# Teensy_board.net
KiCad netlist of a schematic drawn in EAGLE
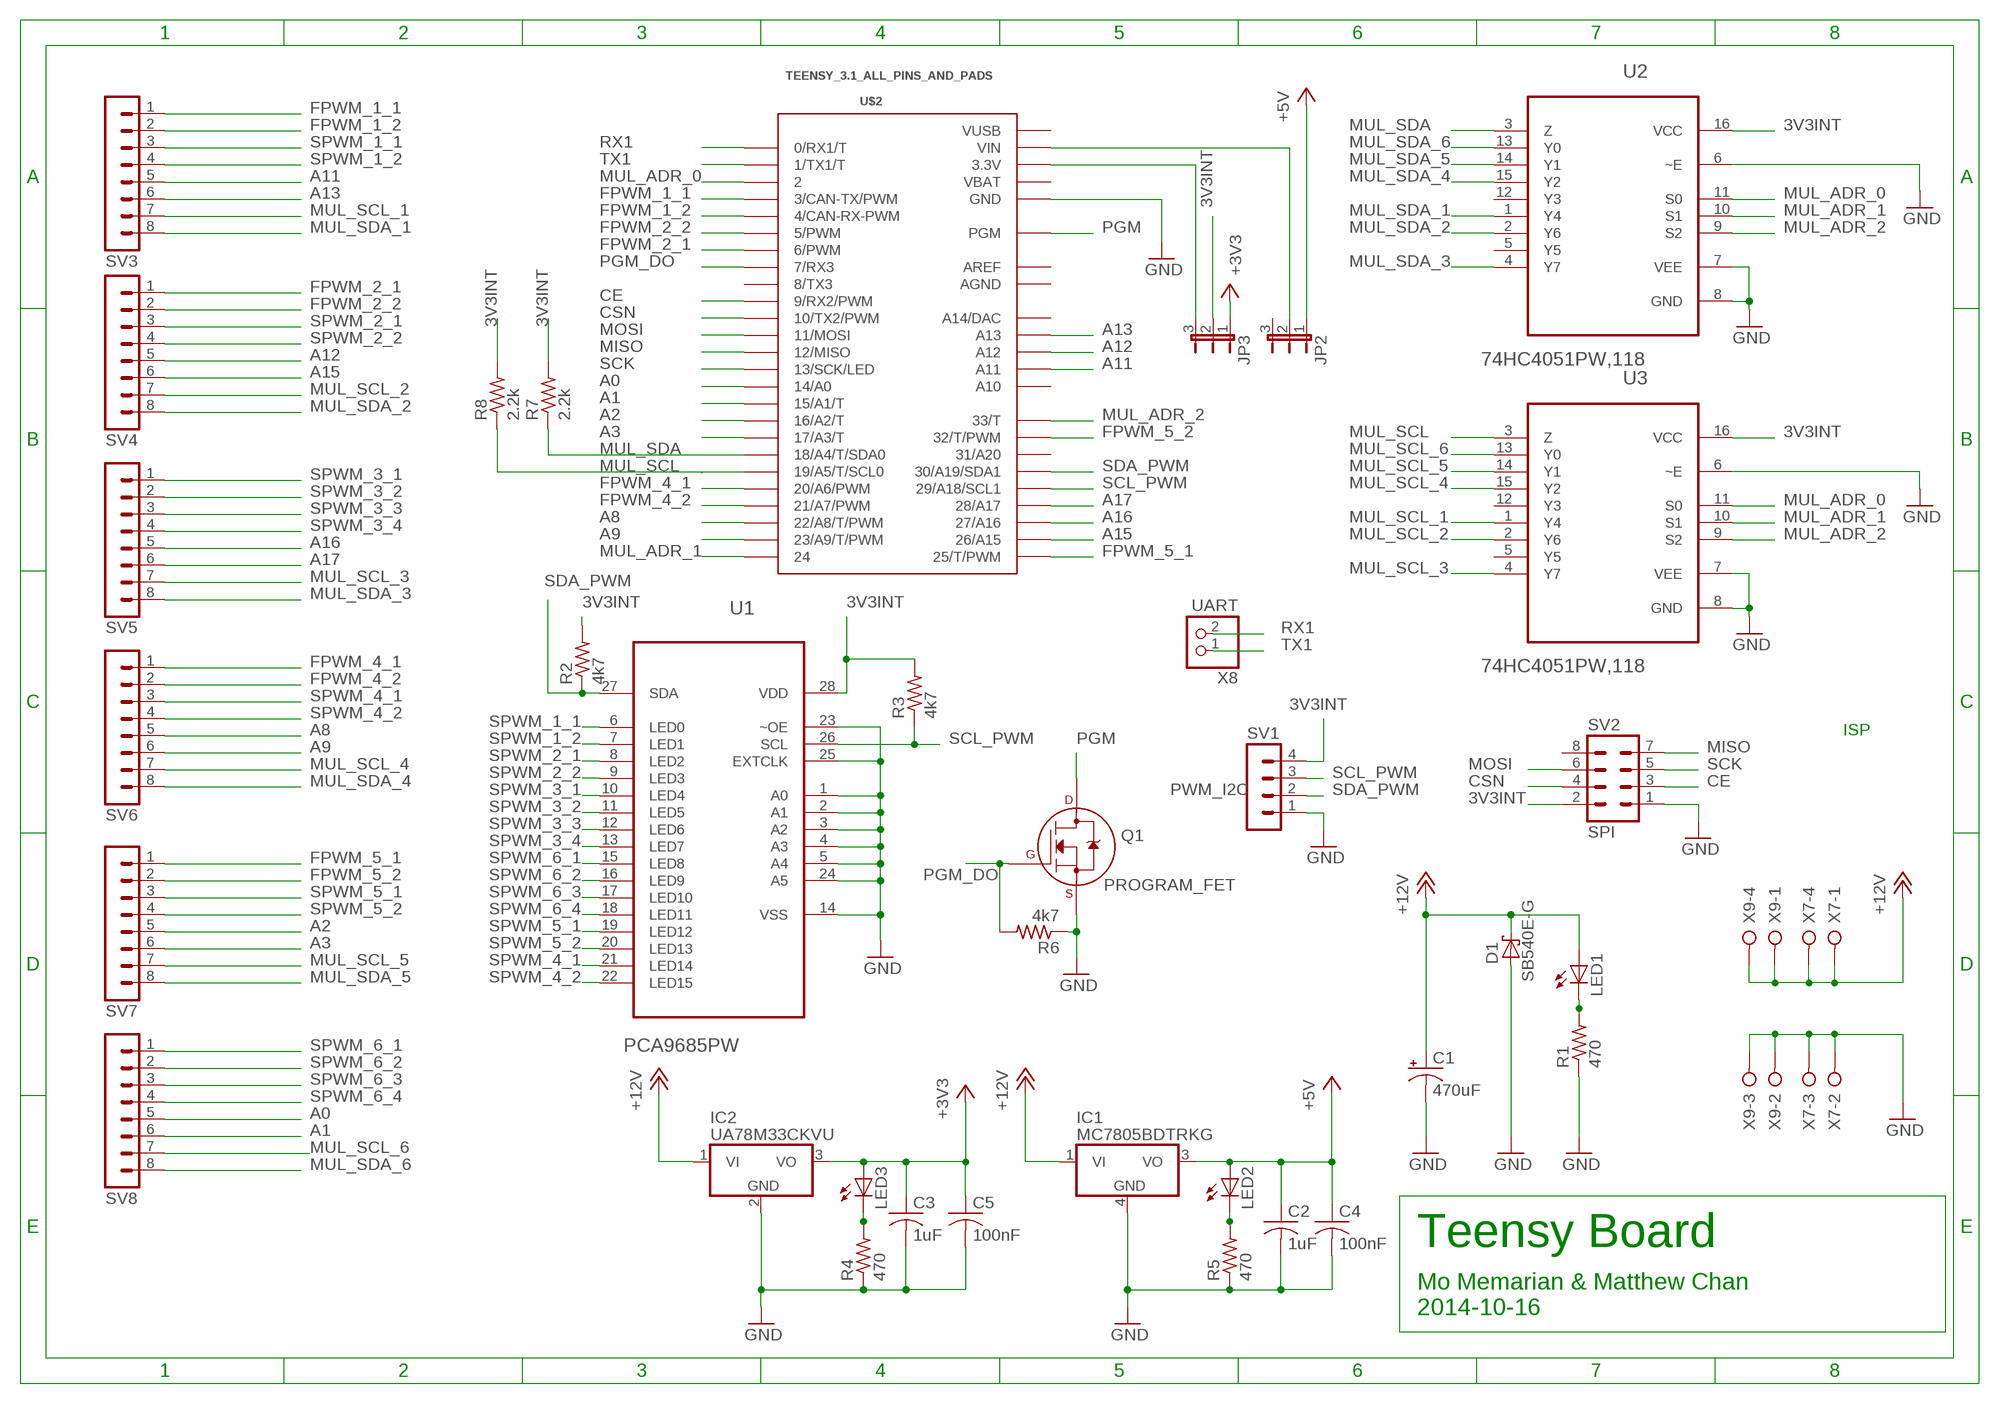
[diagram p0: schematic, sheet 1]

(export (version "E")
  (design (tool "Eeschema 10.0.6"))
  (components
    (comp (ref "C1")
      (value "470uF")
      (footprint "eagle-import:E5-10,5")
      (libsource (lib "eagle-import") (part "CPOL-USE5-10.5"))
    )
    (comp (ref "C2")
      (value "1uF")
      (footprint "eagle-import:C0603")
      (libsource (lib "eagle-import") (part "C-USC0603"))
    )
    (comp (ref "C3")
      (value "1uF")
      (footprint "eagle-import:C0603")
      (libsource (lib "eagle-import") (part "C-USC0603"))
    )
    (comp (ref "C4")
      (value "100nF")
      (footprint "eagle-import:C0603")
      (libsource (lib "eagle-import") (part "C-USC0603"))
    )
    (comp (ref "C5")
      (value "100nF")
      (footprint "eagle-import:C0603")
      (libsource (lib "eagle-import") (part "C-USC0603"))
    )
    (comp (ref "D1")
      (value "SB540E-G")
      (footprint "eagle-import:DO201T15")
      (libsource (lib "eagle-import") (part "SB540E-G"))
    )
    (comp (ref "IC1")
      (value "MC7805BDTRKG")
      (footprint "eagle-import:DPACK_3")
      (libsource (lib "eagle-import") (part "MC7805BDTRKG"))
    )
    (comp (ref "IC2")
      (value "UA78M33CKVU")
      (footprint "eagle-import:DPACK")
      (libsource (lib "eagle-import") (part "UA78MKVU33C"))
    )
    (comp (ref "JP2")
      (value "JP2E")
      (footprint "eagle-import:JP2")
      (libsource (lib "eagle-import") (part "JP2E"))
    )
    (comp (ref "JP3")
      (value "JP2E")
      (footprint "eagle-import:JP2")
      (libsource (lib "eagle-import") (part "JP2E"))
    )
    (comp (ref "LED1")
      (value "LEDSML1206")
      (footprint "eagle-import:SML1206")
      (libsource (lib "eagle-import") (part "LEDSML1206"))
    )
    (comp (ref "LED2")
      (value "LEDSML1206")
      (footprint "eagle-import:SML1206")
      (libsource (lib "eagle-import") (part "LEDSML1206"))
    )
    (comp (ref "LED3")
      (value "LEDSML1206")
      (footprint "eagle-import:SML1206")
      (libsource (lib "eagle-import") (part "LEDSML1206"))
    )
    (comp (ref "Q1")
      (value "PROGRAM_FET")
      (footprint "eagle-import:SOT-23")
      (libsource (lib "eagle-import") (part "2N700_SOT232"))
    )
    (comp (ref "R1")
      (value "470")
      (footprint "eagle-import:R0603")
      (libsource (lib "eagle-import") (part "R-US_R0603"))
    )
    (comp (ref "R2")
      (value "4k7")
      (footprint "eagle-import:R0603")
      (libsource (lib "eagle-import") (part "R-US_R0603"))
    )
    (comp (ref "R3")
      (value "4k7")
      (footprint "eagle-import:R0603")
      (libsource (lib "eagle-import") (part "R-US_R0603"))
    )
    (comp (ref "R4")
      (value "470")
      (footprint "eagle-import:R0603")
      (libsource (lib "eagle-import") (part "R-US_R0603"))
    )
    (comp (ref "R5")
      (value "470")
      (footprint "eagle-import:R0603")
      (libsource (lib "eagle-import") (part "R-US_R0603"))
    )
    (comp (ref "R6")
      (value "4k7")
      (footprint "eagle-import:R0603")
      (libsource (lib "eagle-import") (part "R-US_R0603"))
    )
    (comp (ref "R7")
      (value "2.2k")
      (footprint "eagle-import:R0603")
      (libsource (lib "eagle-import") (part "R-US_R0603"))
    )
    (comp (ref "R8")
      (value "2.2k")
      (footprint "eagle-import:R0603")
      (libsource (lib "eagle-import") (part "R-US_R0603"))
    )
    (comp (ref "SV1")
      (value "PWM_I2C")
      (footprint "eagle-import:MA04-1")
      (libsource (lib "eagle-import") (part "MA04-1"))
    )
    (comp (ref "SV2")
      (value "SPI")
      (footprint "eagle-import:MA04-2")
      (libsource (lib "eagle-import") (part "MA04-2"))
    )
    (comp (ref "SV3")
      (value "MA08-1")
      (footprint "eagle-import:MA08-1")
      (libsource (lib "eagle-import") (part "MA08-1"))
    )
    (comp (ref "SV4")
      (value "MA08-1")
      (footprint "eagle-import:MA08-1")
      (libsource (lib "eagle-import") (part "MA08-1"))
    )
    (comp (ref "SV5")
      (value "MA08-1")
      (footprint "eagle-import:MA08-1")
      (libsource (lib "eagle-import") (part "MA08-1"))
    )
    (comp (ref "SV6")
      (value "MA08-1")
      (footprint "eagle-import:MA08-1")
      (libsource (lib "eagle-import") (part "MA08-1"))
    )
    (comp (ref "SV7")
      (value "MA08-1")
      (footprint "eagle-import:MA08-1")
      (libsource (lib "eagle-import") (part "MA08-1"))
    )
    (comp (ref "SV8")
      (value "MA08-1")
      (footprint "eagle-import:MA08-1")
      (libsource (lib "eagle-import") (part "MA08-1"))
    )
    (comp (ref "U$2")
      (value "TEENSY_3.1_ALL_PINS_AND_PADS")
      (footprint "eagle-import:TEENSY_3.1_ALLPINS")
      (libsource (lib "eagle-import") (part "TEENSY_3.1_ALL_PINS_AND_PADS"))
    )
    (comp (ref "U1")
      (value "PCA9685PW")
      (footprint "eagle-import:SOP65P640X110-28N")
      (libsource (lib "eagle-import") (part "PCA9685PW"))
    )
    (comp (ref "U2")
      (value "74HC4051PW,118")
      (footprint "eagle-import:SOP65P640X110-16N")
      (libsource (lib "eagle-import") (part "74HC4051PW,118"))
    )
    (comp (ref "U3")
      (value "74HC4051PW,118")
      (footprint "eagle-import:SOP65P640X110-16N")
      (libsource (lib "eagle-import") (part "74HC4051PW,118"))
    )
    (comp (ref "X7")
      (value "W237-04P")
      (footprint "eagle-import:W237-4P")
      (libsource (lib "eagle-import") (part "W237-04P"))
    )
    (comp (ref "X8")
      (value "UART")
      (footprint "eagle-import:1X02")
      (libsource (lib "eagle-import") (part "PINHD-1X2"))
    )
    (comp (ref "X9")
      (value "W237-04P")
      (footprint "eagle-import:W237-4P")
      (libsource (lib "eagle-import") (part "W237-04P"))
    )
  )
  (nets
    (net (code "1") (name "+3V3") (class "Default")
      (node (ref "C3") (pin "1") (pinfunction "1_1") (pintype "passive"))
      (node (ref "C5") (pin "1") (pinfunction "1_1") (pintype "passive"))
      (node (ref "IC2") (pin "3") (pinfunction "VO_3") (pintype "passive"))
      (node (ref "JP3") (pin "1") (pinfunction "1_1") (pintype "passive"))
      (node (ref "LED3") (pin "A") (pinfunction "A_A") (pintype "passive"))
    )
    (net (code "2") (name "+5V") (class "Default")
      (node (ref "C2") (pin "1") (pinfunction "1_1") (pintype "passive"))
      (node (ref "C4") (pin "1") (pinfunction "1_1") (pintype "passive"))
      (node (ref "IC1") (pin "3") (pinfunction "VO_3") (pintype "passive"))
      (node (ref "JP2") (pin "1") (pinfunction "1_1") (pintype "passive"))
      (node (ref "LED2") (pin "A") (pinfunction "A_A") (pintype "passive"))
    )
    (net (code "3") (name "+12V") (class "Default")
      (node (ref "C1") (pin "+") (pinfunction "+_+") (pintype "passive"))
      (node (ref "D1") (pin "C") (pinfunction "C_C") (pintype "passive"))
      (node (ref "IC1") (pin "1") (pinfunction "VI_1") (pintype "input"))
      (node (ref "IC2") (pin "1") (pinfunction "VI_1") (pintype "input"))
      (node (ref "LED1") (pin "A") (pinfunction "A_A") (pintype "passive"))
      (node (ref "X7") (pin "1") (pinfunction "KL_1") (pintype "passive"))
      (node (ref "X7") (pin "4") (pinfunction "KL_4") (pintype "passive"))
      (node (ref "X9") (pin "1") (pinfunction "KL_1") (pintype "passive"))
      (node (ref "X9") (pin "4") (pinfunction "KL_4") (pintype "passive"))
    )
    (net (code "4") (name "/3V3INT") (class "Default")
      (node (ref "JP3") (pin "2") (pinfunction "2_2") (pintype "passive"))
      (node (ref "R2") (pin "2") (pinfunction "2_2") (pintype "passive"))
      (node (ref "R3") (pin "2") (pinfunction "2_2") (pintype "passive"))
      (node (ref "R7") (pin "2") (pinfunction "2_2") (pintype "passive"))
      (node (ref "R8") (pin "2") (pinfunction "2_2") (pintype "passive"))
      (node (ref "SV1") (pin "4") (pinfunction "4_4") (pintype "passive"))
      (node (ref "SV2") (pin "2") (pinfunction "2_2") (pintype "passive"))
      (node (ref "U1") (pin "28") (pinfunction "VDD_28") (pintype "power_in"))
      (node (ref "U2") (pin "16") (pinfunction "VCC_16") (pintype "power_in"))
      (node (ref "U3") (pin "16") (pinfunction "VCC_16") (pintype "power_in"))
    )
    (net (code "5") (name "/A0") (class "Default")
      (node (ref "SV8") (pin "5") (pinfunction "5_5") (pintype "passive"))
      (node (ref "U$2") (pin "14/A0") (pinfunction "14/A0_14/A0") (pintype "bidirectional"))
    )
    (net (code "6") (name "/A1") (class "Default")
      (node (ref "SV8") (pin "6") (pinfunction "6_6") (pintype "passive"))
      (node (ref "U$2") (pin "15/A1") (pinfunction "15/A1/T_15/A1") (pintype "bidirectional"))
    )
    (net (code "7") (name "/A2") (class "Default")
      (node (ref "SV7") (pin "5") (pinfunction "5_5") (pintype "passive"))
      (node (ref "U$2") (pin "16/A2") (pinfunction "16/A2/T_16/A2") (pintype "bidirectional"))
    )
    (net (code "8") (name "/A3") (class "Default")
      (node (ref "SV7") (pin "6") (pinfunction "6_6") (pintype "passive"))
      (node (ref "U$2") (pin "17/A3") (pinfunction "17/A3/T_17/A3") (pintype "bidirectional"))
    )
    (net (code "9") (name "/A8") (class "Default")
      (node (ref "SV6") (pin "5") (pinfunction "5_5") (pintype "passive"))
      (node (ref "U$2") (pin "22/A8") (pinfunction "22/A8/T/PWM_22/A8") (pintype "bidirectional"))
    )
    (net (code "10") (name "/A9") (class "Default")
      (node (ref "SV6") (pin "6") (pinfunction "6_6") (pintype "passive"))
      (node (ref "U$2") (pin "23/A9") (pinfunction "23/A9/T/PWM_23/A9") (pintype "bidirectional"))
    )
    (net (code "11") (name "/A11") (class "Default")
      (node (ref "SV3") (pin "5") (pinfunction "5_5") (pintype "passive"))
      (node (ref "U$2") (pin "A11") (pinfunction "A11_A11") (pintype "bidirectional"))
    )
    (net (code "12") (name "/A12") (class "Default")
      (node (ref "SV4") (pin "5") (pinfunction "5_5") (pintype "passive"))
      (node (ref "U$2") (pin "A12") (pinfunction "A12_A12") (pintype "bidirectional"))
    )
    (net (code "13") (name "/A13") (class "Default")
      (node (ref "SV3") (pin "6") (pinfunction "6_6") (pintype "passive"))
      (node (ref "U$2") (pin "A13") (pinfunction "A13_A13") (pintype "bidirectional"))
    )
    (net (code "14") (name "/A15") (class "Default")
      (node (ref "SV4") (pin "6") (pinfunction "6_6") (pintype "passive"))
      (node (ref "U$2") (pin "26") (pinfunction "26/A15_26") (pintype "bidirectional"))
    )
    (net (code "15") (name "/A16") (class "Default")
      (node (ref "SV5") (pin "5") (pinfunction "5_5") (pintype "passive"))
      (node (ref "U$2") (pin "27") (pinfunction "27/A16_27") (pintype "bidirectional"))
    )
    (net (code "16") (name "/A17") (class "Default")
      (node (ref "SV5") (pin "6") (pinfunction "6_6") (pintype "passive"))
      (node (ref "U$2") (pin "28") (pinfunction "28/A17_28") (pintype "bidirectional"))
    )
    (net (code "17") (name "/AGND") (class "Default")
      (node (ref "U$2") (pin "AGND") (pinfunction "AGND_AGND") (pintype "power_in"))
    )
    (net (code "18") (name "/AREF") (class "Default")
      (node (ref "U$2") (pin "AREF") (pinfunction "AREF_AREF") (pintype "power_in"))
    )
    (net (code "19") (name "/CE") (class "Default")
      (node (ref "SV2") (pin "3") (pinfunction "3_3") (pintype "passive"))
      (node (ref "U$2") (pin "9") (pinfunction "9/RX2/PWM_9") (pintype "bidirectional"))
    )
    (net (code "20") (name "/CSN") (class "Default")
      (node (ref "SV2") (pin "4") (pinfunction "4_4") (pintype "passive"))
      (node (ref "U$2") (pin "10") (pinfunction "10/TX2/PWM_10") (pintype "bidirectional"))
    )
    (net (code "21") (name "/FPWM_1_1") (class "Default")
      (node (ref "SV3") (pin "1") (pinfunction "1_1") (pintype "passive"))
      (node (ref "U$2") (pin "3") (pinfunction "3/CAN-TX/PWM_3") (pintype "bidirectional"))
    )
    (net (code "22") (name "/FPWM_1_2") (class "Default")
      (node (ref "SV3") (pin "2") (pinfunction "2_2") (pintype "passive"))
      (node (ref "U$2") (pin "4") (pinfunction "4/CAN-RX-PWM_4") (pintype "bidirectional"))
    )
    (net (code "23") (name "/FPWM_2_1") (class "Default")
      (node (ref "SV4") (pin "1") (pinfunction "1_1") (pintype "passive"))
      (node (ref "U$2") (pin "6") (pinfunction "6/PWM_6") (pintype "bidirectional"))
    )
    (net (code "24") (name "/FPWM_2_2") (class "Default")
      (node (ref "SV4") (pin "2") (pinfunction "2_2") (pintype "passive"))
      (node (ref "U$2") (pin "5") (pinfunction "5/PWM_5") (pintype "bidirectional"))
    )
    (net (code "25") (name "/FPWM_4_1") (class "Default")
      (node (ref "SV6") (pin "1") (pinfunction "1_1") (pintype "passive"))
      (node (ref "U$2") (pin "20/A6") (pinfunction "20/A6/PWM_20/A6") (pintype "bidirectional"))
    )
    (net (code "26") (name "/FPWM_4_2") (class "Default")
      (node (ref "SV6") (pin "2") (pinfunction "2_2") (pintype "passive"))
      (node (ref "U$2") (pin "21/A7") (pinfunction "21/A7/PWM_21/A7") (pintype "bidirectional"))
    )
    (net (code "27") (name "/FPWM_5_1") (class "Default")
      (node (ref "SV7") (pin "1") (pinfunction "1_1") (pintype "passive"))
      (node (ref "U$2") (pin "25") (pinfunction "25/T/PWM_25") (pintype "bidirectional"))
    )
    (net (code "28") (name "/FPWM_5_2") (class "Default")
      (node (ref "SV7") (pin "2") (pinfunction "2_2") (pintype "passive"))
      (node (ref "U$2") (pin "32") (pinfunction "32/T/PWM_32") (pintype "bidirectional"))
    )
    (net (code "29") (name "/MISO") (class "Default")
      (node (ref "SV2") (pin "7") (pinfunction "7_7") (pintype "passive"))
      (node (ref "U$2") (pin "12") (pinfunction "12/MISO_12") (pintype "bidirectional"))
    )
    (net (code "30") (name "/MOSI") (class "Default")
      (node (ref "SV2") (pin "6") (pinfunction "6_6") (pintype "passive"))
      (node (ref "U$2") (pin "11") (pinfunction "11/MOSI_11") (pintype "bidirectional"))
    )
    (net (code "31") (name "/MUL_ADR_0") (class "Default")
      (node (ref "U$2") (pin "2") (pinfunction "2_2") (pintype "bidirectional"))
      (node (ref "U2") (pin "11") (pinfunction "S0_11") (pintype "input"))
      (node (ref "U3") (pin "11") (pinfunction "S0_11") (pintype "input"))
    )
    (net (code "32") (name "/MUL_ADR_1") (class "Default")
      (node (ref "U$2") (pin "24") (pinfunction "24_24") (pintype "bidirectional"))
      (node (ref "U2") (pin "10") (pinfunction "S1_10") (pintype "input"))
      (node (ref "U3") (pin "10") (pinfunction "S1_10") (pintype "input"))
    )
    (net (code "33") (name "/MUL_ADR_2") (class "Default")
      (node (ref "U$2") (pin "33") (pinfunction "33/T_33") (pintype "bidirectional"))
      (node (ref "U2") (pin "9") (pinfunction "S2_9") (pintype "input"))
      (node (ref "U3") (pin "9") (pinfunction "S2_9") (pintype "input"))
    )
    (net (code "34") (name "/MUL_SCL") (class "Default")
      (node (ref "R8") (pin "1") (pinfunction "1_1") (pintype "passive"))
      (node (ref "U$2") (pin "19/A5") (pinfunction "19/A5/T/SCL0_19/A5") (pintype "bidirectional"))
      (node (ref "U3") (pin "3") (pinfunction "Z_3") (pintype "bidirectional"))
    )
    (net (code "35") (name "/MUL_SCL_1") (class "Default")
      (node (ref "SV3") (pin "7") (pinfunction "7_7") (pintype "passive"))
      (node (ref "U3") (pin "1") (pinfunction "Y4_1") (pintype "bidirectional"))
    )
    (net (code "36") (name "/MUL_SCL_2") (class "Default")
      (node (ref "SV4") (pin "7") (pinfunction "7_7") (pintype "passive"))
      (node (ref "U3") (pin "2") (pinfunction "Y6_2") (pintype "bidirectional"))
    )
    (net (code "37") (name "/MUL_SCL_3") (class "Default")
      (node (ref "SV5") (pin "7") (pinfunction "7_7") (pintype "passive"))
      (node (ref "U3") (pin "4") (pinfunction "Y7_4") (pintype "bidirectional"))
    )
    (net (code "38") (name "/MUL_SCL_4") (class "Default")
      (node (ref "SV6") (pin "7") (pinfunction "7_7") (pintype "passive"))
      (node (ref "U3") (pin "15") (pinfunction "Y2_15") (pintype "bidirectional"))
    )
    (net (code "39") (name "/MUL_SCL_5") (class "Default")
      (node (ref "SV7") (pin "7") (pinfunction "7_7") (pintype "passive"))
      (node (ref "U3") (pin "14") (pinfunction "Y1_14") (pintype "bidirectional"))
    )
    (net (code "40") (name "/MUL_SCL_6") (class "Default")
      (node (ref "SV8") (pin "7") (pinfunction "7_7") (pintype "passive"))
      (node (ref "U3") (pin "13") (pinfunction "Y0_13") (pintype "bidirectional"))
    )
    (net (code "41") (name "/MUL_SDA") (class "Default")
      (node (ref "R7") (pin "1") (pinfunction "1_1") (pintype "passive"))
      (node (ref "U$2") (pin "18/A4") (pinfunction "18/A4/T/SDA0_18/A4") (pintype "bidirectional"))
      (node (ref "U2") (pin "3") (pinfunction "Z_3") (pintype "bidirectional"))
    )
    (net (code "42") (name "/MUL_SDA_1") (class "Default")
      (node (ref "SV3") (pin "8") (pinfunction "8_8") (pintype "passive"))
      (node (ref "U2") (pin "1") (pinfunction "Y4_1") (pintype "bidirectional"))
    )
    (net (code "43") (name "/MUL_SDA_2") (class "Default")
      (node (ref "SV4") (pin "8") (pinfunction "8_8") (pintype "passive"))
      (node (ref "U2") (pin "2") (pinfunction "Y6_2") (pintype "bidirectional"))
    )
    (net (code "44") (name "/MUL_SDA_3") (class "Default")
      (node (ref "SV5") (pin "8") (pinfunction "8_8") (pintype "passive"))
      (node (ref "U2") (pin "4") (pinfunction "Y7_4") (pintype "bidirectional"))
    )
    (net (code "45") (name "/MUL_SDA_4") (class "Default")
      (node (ref "SV6") (pin "8") (pinfunction "8_8") (pintype "passive"))
      (node (ref "U2") (pin "15") (pinfunction "Y2_15") (pintype "bidirectional"))
    )
    (net (code "46") (name "/MUL_SDA_5") (class "Default")
      (node (ref "SV7") (pin "8") (pinfunction "8_8") (pintype "passive"))
      (node (ref "U2") (pin "14") (pinfunction "Y1_14") (pintype "bidirectional"))
    )
    (net (code "47") (name "/MUL_SDA_6") (class "Default")
      (node (ref "SV8") (pin "8") (pinfunction "8_8") (pintype "passive"))
      (node (ref "U2") (pin "13") (pinfunction "Y0_13") (pintype "bidirectional"))
    )
    (net (code "48") (name "/PGM") (class "Default")
      (node (ref "Q1") (pin "3") (pinfunction "D_3") (pintype "bidirectional"))
      (node (ref "U$2") (pin "PGM") (pinfunction "PGM_PGM") (pintype "bidirectional"))
    )
    (net (code "49") (name "/PGM_DO") (class "Default")
      (node (ref "Q1") (pin "1") (pinfunction "G_1") (pintype "tri_state"))
      (node (ref "R6") (pin "2") (pinfunction "2_2") (pintype "passive"))
      (node (ref "U$2") (pin "7") (pinfunction "7/RX3_7") (pintype "bidirectional"))
    )
    (net (code "50") (name "/RX1") (class "Default")
      (node (ref "U$2") (pin "0") (pinfunction "0/RX1/T_0") (pintype "bidirectional"))
      (node (ref "X8") (pin "2") (pinfunction "2_2") (pintype "passive"))
    )
    (net (code "51") (name "/SCK") (class "Default")
      (node (ref "SV2") (pin "5") (pinfunction "5_5") (pintype "passive"))
      (node (ref "U$2") (pin "13") (pinfunction "13/SCK/LED_13") (pintype "bidirectional"))
    )
    (net (code "52") (name "/SCL_PWM") (class "Default")
      (node (ref "R3") (pin "1") (pinfunction "1_1") (pintype "passive"))
      (node (ref "SV1") (pin "3") (pinfunction "3_3") (pintype "passive"))
      (node (ref "U$2") (pin "29") (pinfunction "29/A18/SCL1_29") (pintype "bidirectional"))
      (node (ref "U1") (pin "26") (pinfunction "SCL_26") (pintype "input"))
    )
    (net (code "53") (name "/SDA_PWM") (class "Default")
      (node (ref "R2") (pin "1") (pinfunction "1_1") (pintype "passive"))
      (node (ref "SV1") (pin "2") (pinfunction "2_2") (pintype "passive"))
      (node (ref "U$2") (pin "30") (pinfunction "30/A19/SDA1_30") (pintype "bidirectional"))
      (node (ref "U1") (pin "27") (pinfunction "SDA_27") (pintype "bidirectional"))
    )
    (net (code "54") (name "/SPWM_1_1") (class "Default")
      (node (ref "SV3") (pin "3") (pinfunction "3_3") (pintype "passive"))
      (node (ref "U1") (pin "6") (pinfunction "LED0_6") (pintype "output"))
    )
    (net (code "55") (name "/SPWM_1_2") (class "Default")
      (node (ref "SV3") (pin "4") (pinfunction "4_4") (pintype "passive"))
      (node (ref "U1") (pin "7") (pinfunction "LED1_7") (pintype "output"))
    )
    (net (code "56") (name "/SPWM_2_1") (class "Default")
      (node (ref "SV4") (pin "3") (pinfunction "3_3") (pintype "passive"))
      (node (ref "U1") (pin "8") (pinfunction "LED2_8") (pintype "output"))
    )
    (net (code "57") (name "/SPWM_2_2") (class "Default")
      (node (ref "SV4") (pin "4") (pinfunction "4_4") (pintype "passive"))
      (node (ref "U1") (pin "9") (pinfunction "LED3_9") (pintype "output"))
    )
    (net (code "58") (name "/SPWM_3_1") (class "Default")
      (node (ref "SV5") (pin "1") (pinfunction "1_1") (pintype "passive"))
      (node (ref "U1") (pin "10") (pinfunction "LED4_10") (pintype "output"))
    )
    (net (code "59") (name "/SPWM_3_2") (class "Default")
      (node (ref "SV5") (pin "2") (pinfunction "2_2") (pintype "passive"))
      (node (ref "U1") (pin "11") (pinfunction "LED5_11") (pintype "output"))
    )
    (net (code "60") (name "/SPWM_3_3") (class "Default")
      (node (ref "SV5") (pin "3") (pinfunction "3_3") (pintype "passive"))
      (node (ref "U1") (pin "12") (pinfunction "LED6_12") (pintype "output"))
    )
    (net (code "61") (name "/SPWM_3_4") (class "Default")
      (node (ref "SV5") (pin "4") (pinfunction "4_4") (pintype "passive"))
      (node (ref "U1") (pin "13") (pinfunction "LED7_13") (pintype "output"))
    )
    (net (code "62") (name "/SPWM_4_1") (class "Default")
      (node (ref "SV6") (pin "3") (pinfunction "3_3") (pintype "passive"))
      (node (ref "U1") (pin "21") (pinfunction "LED14_21") (pintype "output"))
    )
    (net (code "63") (name "/SPWM_4_2") (class "Default")
      (node (ref "SV6") (pin "4") (pinfunction "4_4") (pintype "passive"))
      (node (ref "U1") (pin "22") (pinfunction "LED15_22") (pintype "output"))
    )
    (net (code "64") (name "/SPWM_5_1") (class "Default")
      (node (ref "SV7") (pin "3") (pinfunction "3_3") (pintype "passive"))
      (node (ref "U1") (pin "19") (pinfunction "LED12_19") (pintype "output"))
    )
    (net (code "65") (name "/SPWM_5_2") (class "Default")
      (node (ref "SV7") (pin "4") (pinfunction "4_4") (pintype "passive"))
      (node (ref "U1") (pin "20") (pinfunction "LED13_20") (pintype "output"))
    )
    (net (code "66") (name "/SPWM_6_1") (class "Default")
      (node (ref "SV8") (pin "1") (pinfunction "1_1") (pintype "passive"))
      (node (ref "U1") (pin "15") (pinfunction "LED8_15") (pintype "output"))
    )
    (net (code "67") (name "/SPWM_6_2") (class "Default")
      (node (ref "SV8") (pin "2") (pinfunction "2_2") (pintype "passive"))
      (node (ref "U1") (pin "16") (pinfunction "LED9_16") (pintype "output"))
    )
    (net (code "68") (name "/SPWM_6_3") (class "Default")
      (node (ref "SV8") (pin "3") (pinfunction "3_3") (pintype "passive"))
      (node (ref "U1") (pin "17") (pinfunction "LED10_17") (pintype "output"))
    )
    (net (code "69") (name "/SPWM_6_4") (class "Default")
      (node (ref "SV8") (pin "4") (pinfunction "4_4") (pintype "passive"))
      (node (ref "U1") (pin "18") (pinfunction "LED11_18") (pintype "output"))
    )
    (net (code "70") (name "/TX1") (class "Default")
      (node (ref "U$2") (pin "1") (pinfunction "1/TX1/T_1") (pintype "bidirectional"))
      (node (ref "X8") (pin "1") (pinfunction "1_1") (pintype "passive"))
    )
    (net (code "71") (name "/VBAT") (class "Default")
      (node (ref "U$2") (pin "VBAT") (pinfunction "VBAT_VBAT") (pintype "power_in"))
    )
    (net (code "72") (name "/VUSB") (class "Default")
      (node (ref "U$2") (pin "VUSB") (pinfunction "VUSB_VUSB") (pintype "power_in"))
    )
    (net (code "73") (name "GND") (class "Default")
      (node (ref "C1") (pin "-") (pinfunction "-_-") (pintype "passive"))
      (node (ref "C2") (pin "2") (pinfunction "2_2") (pintype "passive"))
      (node (ref "C3") (pin "2") (pinfunction "2_2") (pintype "passive"))
      (node (ref "C4") (pin "2") (pinfunction "2_2") (pintype "passive"))
      (node (ref "C5") (pin "2") (pinfunction "2_2") (pintype "passive"))
      (node (ref "D1") (pin "A") (pinfunction "A_A") (pintype "passive"))
      (node (ref "IC1") (pin "4") (pinfunction "GND_4") (pintype "passive"))
      (node (ref "IC2") (pin "2") (pinfunction "GND_2") (pintype "passive"))
      (node (ref "Q1") (pin "2") (pinfunction "S_2") (pintype "bidirectional"))
      (node (ref "R1") (pin "1") (pinfunction "1_1") (pintype "passive"))
      (node (ref "R4") (pin "1") (pinfunction "1_1") (pintype "passive"))
      (node (ref "R5") (pin "1") (pinfunction "1_1") (pintype "passive"))
      (node (ref "R6") (pin "1") (pinfunction "1_1") (pintype "passive"))
      (node (ref "SV1") (pin "1") (pinfunction "1_1") (pintype "passive"))
      (node (ref "SV2") (pin "1") (pinfunction "1_1") (pintype "passive"))
      (node (ref "U$2") (pin "GND") (pinfunction "GND_GND") (pintype "power_in"))
      (node (ref "U$2") (pin "GND1") (pinfunction "GND_GND1") (pintype "power_in"))
      (node (ref "U$2") (pin "GND2") (pinfunction "GND_GND2") (pintype "power_in"))
      (node (ref "U1") (pin "1") (pinfunction "A0_1") (pintype "input"))
      (node (ref "U1") (pin "14") (pinfunction "VSS_14") (pintype "passive"))
      (node (ref "U1") (pin "2") (pinfunction "A1_2") (pintype "input"))
      (node (ref "U1") (pin "23") (pinfunction "~{OE}_23") (pintype "input"))
      (node (ref "U1") (pin "24") (pinfunction "A5_24") (pintype "input"))
      (node (ref "U1") (pin "25") (pinfunction "EXTCLK_25") (pintype "input"))
      (node (ref "U1") (pin "3") (pinfunction "A2_3") (pintype "input"))
      (node (ref "U1") (pin "4") (pinfunction "A3_4") (pintype "input"))
      (node (ref "U1") (pin "5") (pinfunction "A4_5") (pintype "input"))
      (node (ref "U2") (pin "6") (pinfunction "~{E}_6") (pintype "input"))
      (node (ref "U2") (pin "7") (pinfunction "VEE_7") (pintype "power_in"))
      (node (ref "U2") (pin "8") (pinfunction "GND_8") (pintype "passive"))
      (node (ref "U3") (pin "6") (pinfunction "~{E}_6") (pintype "input"))
      (node (ref "U3") (pin "7") (pinfunction "VEE_7") (pintype "power_in"))
      (node (ref "U3") (pin "8") (pinfunction "GND_8") (pintype "passive"))
      (node (ref "X7") (pin "2") (pinfunction "KL_2") (pintype "passive"))
      (node (ref "X7") (pin "3") (pinfunction "KL_3") (pintype "passive"))
      (node (ref "X9") (pin "2") (pinfunction "KL_2") (pintype "passive"))
      (node (ref "X9") (pin "3") (pinfunction "KL_3") (pintype "passive"))
    )
    (net (code "74") (name "Net-(JP2-Pad2)") (class "Default")
      (node (ref "JP2") (pin "2") (pinfunction "2_2") (pintype "passive"))
      (node (ref "U$2") (pin "VIN") (pinfunction "VIN_VIN") (pintype "power_in"))
    )
    (net (code "75") (name "Net-(JP3-Pad3)") (class "Default")
      (node (ref "JP3") (pin "3") (pinfunction "3_3") (pintype "passive"))
      (node (ref "U$2") (pin "3.3V") (pinfunction "3.3V_3.3V") (pintype "power_in"))
      (node (ref "U$2") (pin "3.3V1") (pinfunction "3.3V_3.3V1") (pintype "power_in"))
      (node (ref "U$2") (pin "3.3V2") (pinfunction "3.3V_3.3V2") (pintype "power_in"))
    )
    (net (code "76") (name "Net-(LED1-PadC)") (class "Default")
      (node (ref "LED1") (pin "C") (pinfunction "C_C") (pintype "passive"))
      (node (ref "R1") (pin "2") (pinfunction "2_2") (pintype "passive"))
    )
    (net (code "77") (name "Net-(LED2-PadC)") (class "Default")
      (node (ref "LED2") (pin "C") (pinfunction "C_C") (pintype "passive"))
      (node (ref "R5") (pin "2") (pinfunction "2_2") (pintype "passive"))
    )
    (net (code "78") (name "Net-(LED3-PadC)") (class "Default")
      (node (ref "LED3") (pin "C") (pinfunction "C_C") (pintype "passive"))
      (node (ref "R4") (pin "2") (pinfunction "2_2") (pintype "passive"))
    )
    (net (code "79") (name "unconnected-(JP2-Pad3)") (class "Default")
      (node (ref "JP2") (pin "3") (pinfunction "3_3") (pintype "passive"))
    )
    (net (code "80") (name "unconnected-(SV2-Pad8)") (class "Default")
      (node (ref "SV2") (pin "8") (pinfunction "8_8") (pintype "passive"))
    )
    (net (code "81") (name "unconnected-(U$2-8{slash}TX3-Pad8)") (class "Default")
      (node (ref "U$2") (pin "8") (pinfunction "8/TX3_8") (pintype "bidirectional"))
    )
    (net (code "82") (name "unconnected-(U$2-31{slash}A20-Pad31)") (class "Default")
      (node (ref "U$2") (pin "31") (pinfunction "31/A20_31") (pintype "bidirectional"))
    )
    (net (code "83") (name "unconnected-(U$2-A14{slash}DAC-PadA14)") (class "Default")
      (node (ref "U$2") (pin "A14") (pinfunction "A14/DAC_A14") (pintype "bidirectional"))
    )
    (net (code "84") (name "unconnected-(U$2-PadA10)") (class "Default")
      (node (ref "U$2") (pin "A10") (pinfunction "A10_A10") (pintype "bidirectional"))
    )
    (net (code "85") (name "unconnected-(U2-Y3-Pad12)") (class "Default")
      (node (ref "U2") (pin "12") (pinfunction "Y3_12") (pintype "bidirectional"))
    )
    (net (code "86") (name "unconnected-(U2-Y5-Pad5)") (class "Default")
      (node (ref "U2") (pin "5") (pinfunction "Y5_5") (pintype "bidirectional"))
    )
    (net (code "87") (name "unconnected-(U3-Y3-Pad12)") (class "Default")
      (node (ref "U3") (pin "12") (pinfunction "Y3_12") (pintype "bidirectional"))
    )
    (net (code "88") (name "unconnected-(U3-Y5-Pad5)") (class "Default")
      (node (ref "U3") (pin "5") (pinfunction "Y5_5") (pintype "bidirectional"))
    )
  )
)
